# SCH_ESP_weather_Cube_2022-04-09.net
KiCad netlist of a schematic drawn in EasyEDA
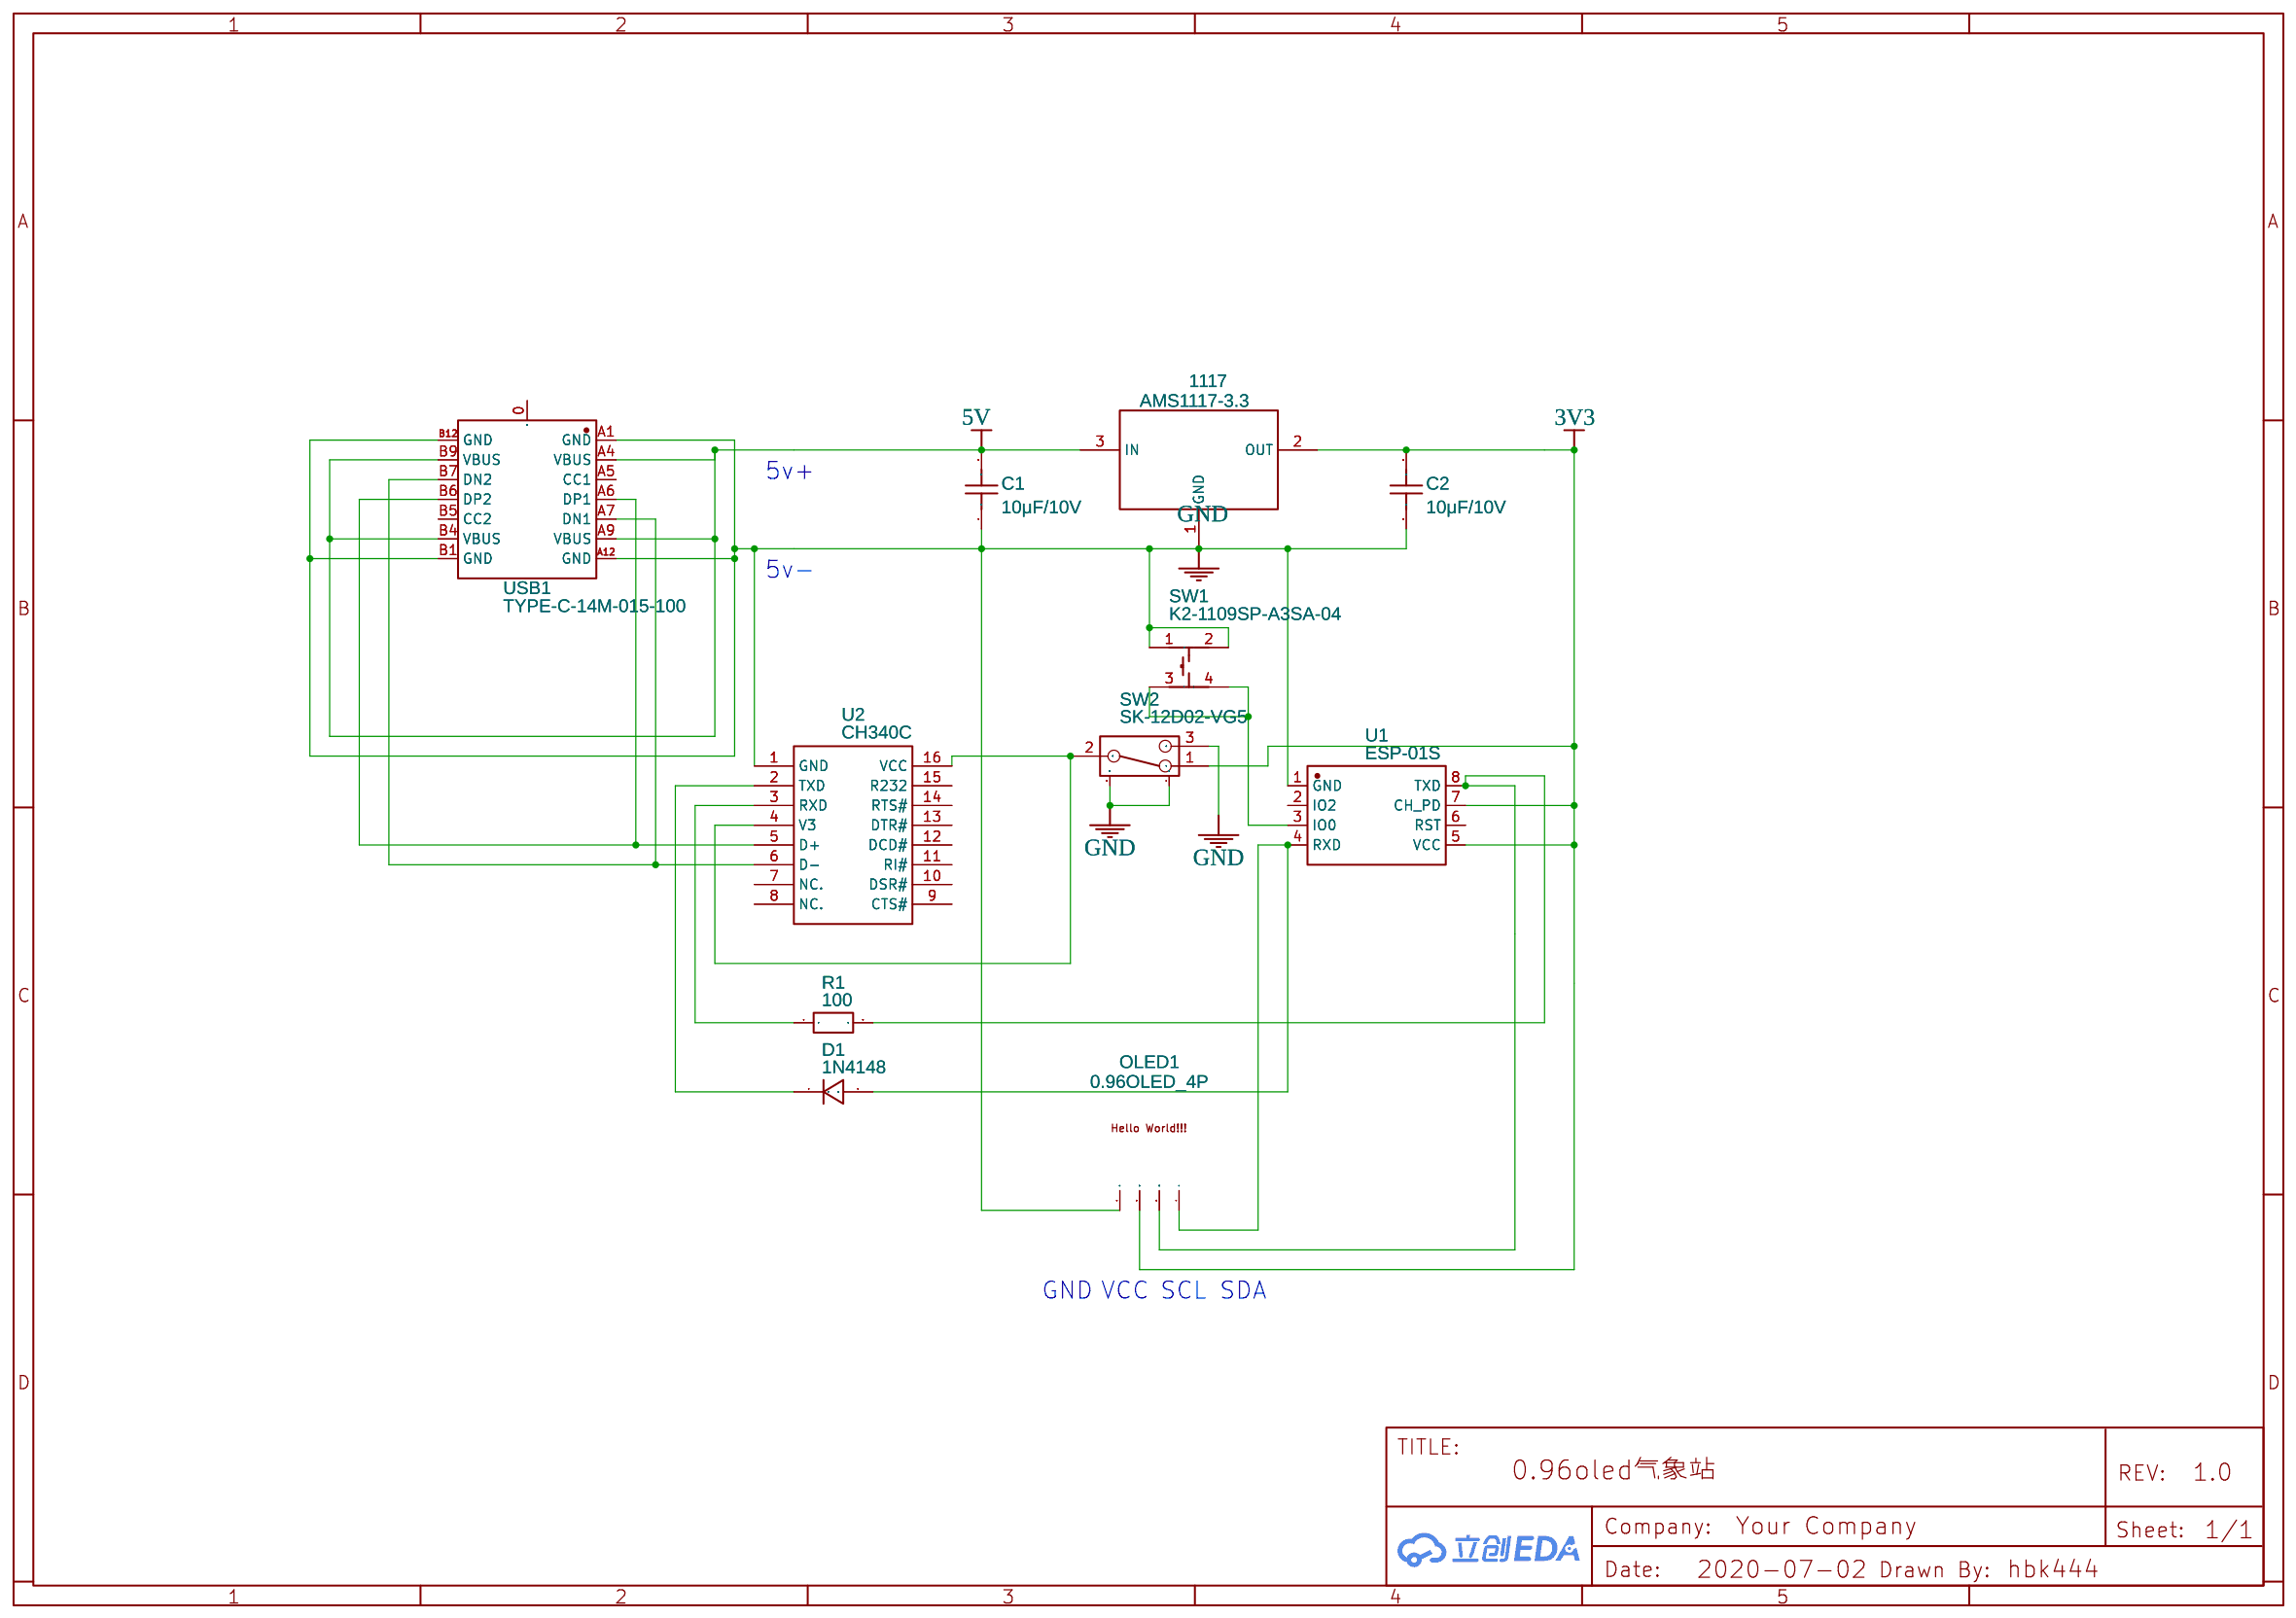
[diagram p0: schematic sheet]

(export (version "E")
  (design (tool "Eeschema 10.0.6"))
  (components
    (comp (ref "1117") (value "AMS1117-3.3") (libsource (lib "") (part "Unknown_560_-605")))
    (comp (ref "C1") (value "10μF/10V") (libsource (lib "") (part "Capacitor")))
    (comp (ref "C2") (value "10μF/10V") (libsource (lib "") (part "Capacitor")))
    (comp (ref "D1")
      (value "1N4148")
      (fields (field (name "BOM_Supplier Part") "C13769"))
      (libsource (lib "") (part "1N4148"))
    )
    (comp (ref "OLED1") (value "0.96OLED_4P") (libsource (lib "") (part "0.96OLED_4P")))
    (comp (ref "R1") (value "100") (libsource (lib "") (part "R_0603_EU")))
    (comp (ref "SW1")
      (value "K2-1109SP-A3SA-04")
      (fields (field (name "BOM_Supplier Part") "C516447"))
      (libsource (lib "") (part "K2-1109SP-A3SA-04"))
    )
    (comp (ref "SW2")
      (value "SK-12D02-VG5")
      (fields (field (name "BOM_Supplier Part") "C136722"))
      (libsource (lib "") (part "SK-12D02-VG5"))
    )
    (comp (ref "U1")
      (value "ESP-01S")
      (fields (field (name "BOM_Supplier Part") "C111009"))
      (libsource (lib "") (part "ESP-01S"))
    )
    (comp (ref "U2")
      (value "CH340C")
      (fields (field (name "BOM_Supplier Part") "C84681"))
      (libsource (lib "") (part "CH340C"))
    )
    (comp (ref "USB1")
      (value "TYPE-C-14M-015-100")
      (fields (field (name "BOM_Supplier Part") "C2798183"))
      (libsource (lib "") (part "TYPE-C-14M-015-100"))
    )
  )
  (nets
    (net (code "1") (name "3V3") (class "Default")
      (node (ref "1117") (pin "2") (pinfunction "OUT_2") (pintype "unspecified"))
      (node (ref "C2") (pin "2") (pinfunction "2_2") (pintype "unspecified"))
      (node (ref "OLED1") (pin "2") (pinfunction "2_2") (pintype "unspecified"))
      (node (ref "SW2") (pin "1") (pinfunction "1_1") (pintype "unspecified"))
      (node (ref "U1") (pin "5") (pinfunction "VCC_5") (pintype "unspecified"))
      (node (ref "U1") (pin "7") (pinfunction "CH_PD_7") (pintype "unspecified"))
    )
    (net (code "2") (name "5V") (class "Default")
      (node (ref "1117") (pin "3") (pinfunction "IN_3") (pintype "unspecified"))
      (node (ref "C1") (pin "2") (pinfunction "2_2") (pintype "unspecified"))
      (node (ref "USB1") (pin "A4") (pinfunction "VBUS_A4") (pintype "unspecified"))
      (node (ref "USB1") (pin "A9") (pinfunction "VBUS_A9") (pintype "unspecified"))
      (node (ref "USB1") (pin "B4") (pinfunction "VBUS_B4") (pintype "unspecified"))
      (node (ref "USB1") (pin "B9") (pinfunction "VBUS_B9") (pintype "unspecified"))
    )
    (net (code "3") (name "GND") (class "Default")
      (node (ref "1117") (pin "1") (pinfunction "GND_1") (pintype "unspecified"))
      (node (ref "C1") (pin "1") (pinfunction "1_1") (pintype "unspecified"))
      (node (ref "C2") (pin "1") (pinfunction "1_1") (pintype "unspecified"))
      (node (ref "OLED1") (pin "1") (pinfunction "1_1") (pintype "unspecified"))
      (node (ref "SW1") (pin "1") (pinfunction "1_1") (pintype "unspecified"))
      (node (ref "SW1") (pin "2") (pinfunction "2_2") (pintype "unspecified"))
      (node (ref "SW2") (pin "3") (pinfunction "3_3") (pintype "unspecified"))
      (node (ref "SW2") (pin "4") (pinfunction "4_4") (pintype "unspecified"))
      (node (ref "SW2") (pin "5") (pinfunction "5_5") (pintype "unspecified"))
      (node (ref "U1") (pin "1") (pinfunction "GND_1") (pintype "unspecified"))
      (node (ref "U2") (pin "1") (pinfunction "GND_1") (pintype "unspecified"))
      (node (ref "USB1") (pin "A1") (pinfunction "GND_A1") (pintype "unspecified"))
      (node (ref "USB1") (pin "A12") (pinfunction "GND_A12") (pintype "unspecified"))
      (node (ref "USB1") (pin "B1") (pinfunction "GND_B1") (pintype "unspecified"))
      (node (ref "USB1") (pin "B12") (pinfunction "GND_B12") (pintype "unspecified"))
    )
    (net (code "4") (name "Net-(U1-IO0)") (class "Default")
      (node (ref "SW1") (pin "3") (pinfunction "3_3") (pintype "unspecified"))
      (node (ref "SW1") (pin "4") (pinfunction "4_4") (pintype "unspecified"))
      (node (ref "U1") (pin "3") (pinfunction "IO0_3") (pintype "unspecified"))
    )
    (net (code "5") (name "Net-(U1-RXD)") (class "Default")
      (node (ref "D1") (pin "2") (pinfunction "2_2") (pintype "unspecified"))
      (node (ref "OLED1") (pin "4") (pinfunction "4_4") (pintype "unspecified"))
      (node (ref "U1") (pin "4") (pinfunction "RXD_4") (pintype "unspecified"))
    )
    (net (code "6") (name "Net-(U1-TXD)") (class "Default")
      (node (ref "OLED1") (pin "3") (pinfunction "3_3") (pintype "unspecified"))
      (node (ref "R1") (pin "2") (pinfunction "2_2") (pintype "unspecified"))
      (node (ref "U1") (pin "8") (pinfunction "TXD_8") (pintype "unspecified"))
    )
    (net (code "7") (name "Net-(U2-D+)") (class "Default")
      (node (ref "U2") (pin "5") (pinfunction "D+_5") (pintype "unspecified"))
      (node (ref "USB1") (pin "A6") (pinfunction "DP1_A6") (pintype "unspecified"))
      (node (ref "USB1") (pin "B6") (pinfunction "DP2_B6") (pintype "unspecified"))
    )
    (net (code "8") (name "Net-(U2-D-)") (class "Default")
      (node (ref "U2") (pin "6") (pinfunction "D-_6") (pintype "unspecified"))
      (node (ref "USB1") (pin "A7") (pinfunction "DN1_A7") (pintype "unspecified"))
      (node (ref "USB1") (pin "B7") (pinfunction "DN2_B7") (pintype "unspecified"))
    )
    (net (code "9") (name "Net-(U2-RXD)") (class "Default")
      (node (ref "R1") (pin "1") (pinfunction "1_1") (pintype "unspecified"))
      (node (ref "U2") (pin "3") (pinfunction "RXD_3") (pintype "unspecified"))
    )
    (net (code "10") (name "Net-(U2-TXD)") (class "Default")
      (node (ref "D1") (pin "1") (pinfunction "1_1") (pintype "unspecified"))
      (node (ref "U2") (pin "2") (pinfunction "TXD_2") (pintype "unspecified"))
    )
    (net (code "11") (name "Net-(U2-V3)") (class "Default")
      (node (ref "SW2") (pin "2") (pinfunction "2_2") (pintype "unspecified"))
      (node (ref "U2") (pin "16") (pinfunction "VCC_16") (pintype "unspecified"))
      (node (ref "U2") (pin "4") (pinfunction "V3_4") (pintype "unspecified"))
    )
    (net (code "12") (name "unconnected-(U1-IO2-Pad2)") (class "Default")
      (node (ref "U1") (pin "2") (pinfunction "IO2_2") (pintype "unspecified"))
    )
    (net (code "13") (name "unconnected-(U1-RST-Pad6)") (class "Default")
      (node (ref "U1") (pin "6") (pinfunction "RST_6") (pintype "unspecified"))
    )
    (net (code "14") (name "unconnected-(U2-CTS#-Pad9)") (class "Default")
      (node (ref "U2") (pin "9") (pinfunction "CTS#_9") (pintype "unspecified"))
    )
    (net (code "15") (name "unconnected-(U2-DCD#-Pad12)") (class "Default")
      (node (ref "U2") (pin "12") (pinfunction "DCD#_12") (pintype "unspecified"))
    )
    (net (code "16") (name "unconnected-(U2-DSR#-Pad10)") (class "Default")
      (node (ref "U2") (pin "10") (pinfunction "DSR#_10") (pintype "unspecified"))
    )
    (net (code "17") (name "unconnected-(U2-DTR#-Pad13)") (class "Default")
      (node (ref "U2") (pin "13") (pinfunction "DTR#_13") (pintype "unspecified"))
    )
    (net (code "18") (name "unconnected-(U2-NC.-Pad7)") (class "Default")
      (node (ref "U2") (pin "7") (pinfunction "NC._7") (pintype "unspecified"))
    )
    (net (code "19") (name "unconnected-(U2-NC.-Pad8)") (class "Default")
      (node (ref "U2") (pin "8") (pinfunction "NC._8") (pintype "unspecified"))
    )
    (net (code "20") (name "unconnected-(U2-R232-Pad15)") (class "Default")
      (node (ref "U2") (pin "15") (pinfunction "R232_15") (pintype "unspecified"))
    )
    (net (code "21") (name "unconnected-(U2-RI#-Pad11)") (class "Default")
      (node (ref "U2") (pin "11") (pinfunction "RI#_11") (pintype "unspecified"))
    )
    (net (code "22") (name "unconnected-(U2-RTS#-Pad14)") (class "Default")
      (node (ref "U2") (pin "14") (pinfunction "RTS#_14") (pintype "unspecified"))
    )
    (net (code "23") (name "unconnected-(USB1-CC1-PadA5)") (class "Default")
      (node (ref "USB1") (pin "A5") (pinfunction "CC1_A5") (pintype "unspecified"))
    )
    (net (code "24") (name "unconnected-(USB1-CC2-PadB5)") (class "Default")
      (node (ref "USB1") (pin "B5") (pinfunction "CC2_B5") (pintype "unspecified"))
    )
    (net (code "25") (name "unconnected-(USB1-Pad0)") (class "Default")
      (node (ref "USB1") (pin "0") (pinfunction "0_0") (pintype "unspecified"))
    )
  )
)
